# Led7_Segment_Receive.net
KiCad netlist of a schematic drawn in Altium Designer
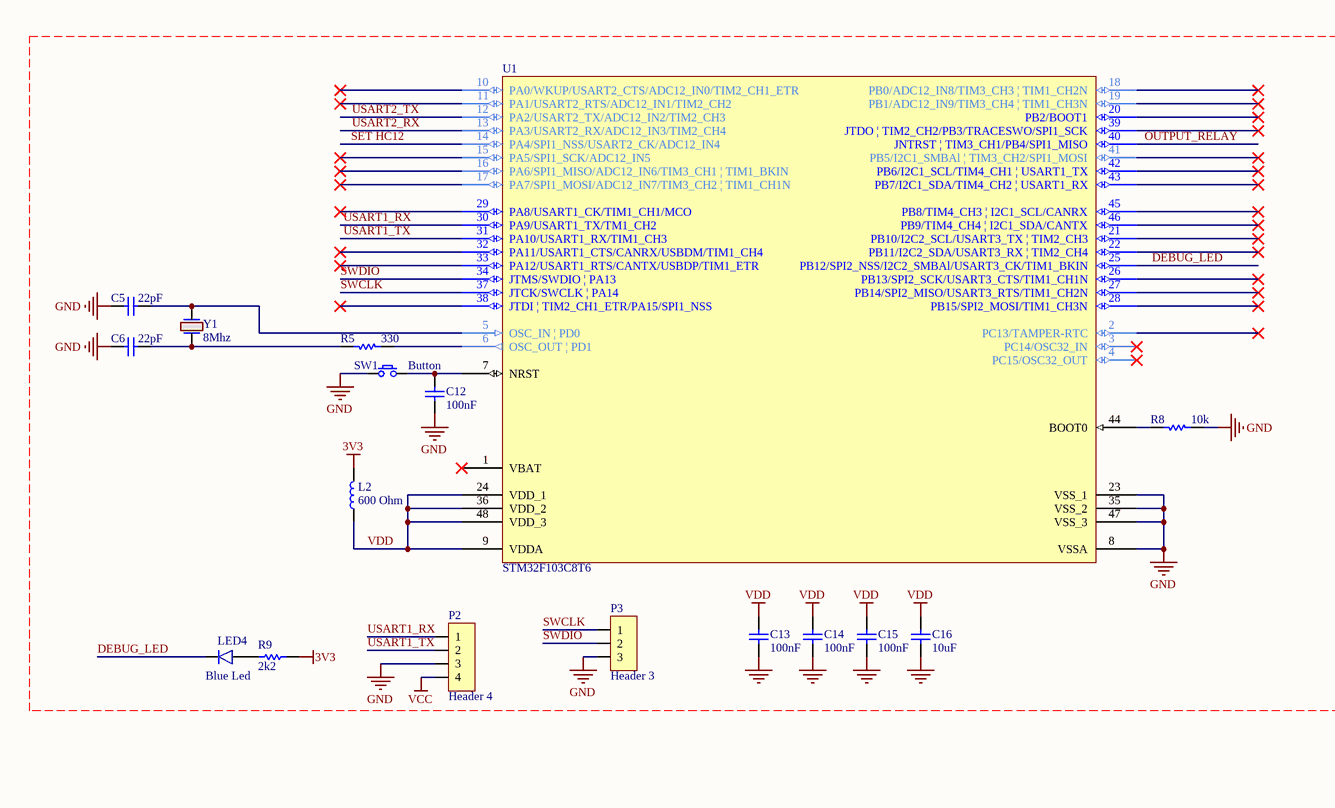
[diagram p0: Led7_Segment_Receive.SchDoc, left]
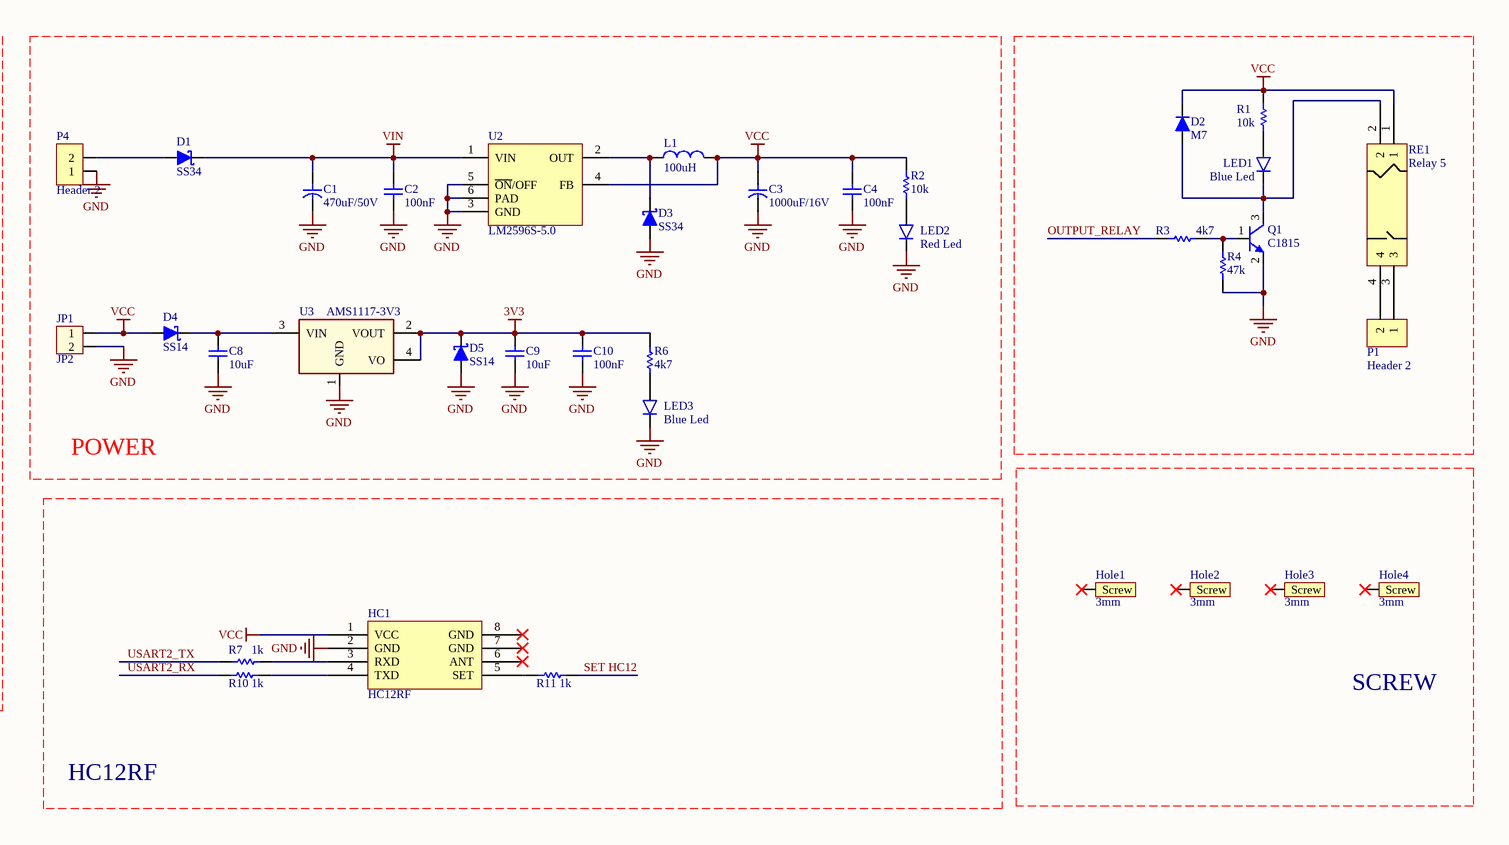
[diagram p1: Led7_Segment_Receive.SchDoc, right]

(export (version "E")
  (design (tool "Eeschema 10.0.6"))
  (components
    (comp (ref "C1")
      (value "470uF/50V")
      (footprint "CR/D.10.0x16.0/P.5.0")
      (description "Capacitor pol")
      (libsource (lib "BKIT4U_LIB") (part "Capacitor"))
    )
    (comp (ref "C2")
      (value "100nF")
      (footprint "C 0805 (2012)")
      (description "Capacitor non-pol")
      (libsource (lib "BKIT4U_LIB") (part "Capacitor NP"))
    )
    (comp (ref "C3")
      (value "1000uF/16V")
      (footprint "CR/D.10.0x12.5/P.5.0")
      (description "Capacitor pol")
      (libsource (lib "BKIT4U_LIB") (part "Capacitor"))
    )
    (comp (ref "C4")
      (value "100nF")
      (footprint "C 0805 (2012)")
      (description "Capacitor non-pol")
      (libsource (lib "BKIT4U_LIB") (part "Capacitor NP"))
    )
    (comp (ref "C5")
      (value "22pF")
      (footprint "C 0805 (2012)")
      (description "Capacitor non-pol")
      (libsource (lib "BKIT4U_LIB") (part "Capacitor NP"))
    )
    (comp (ref "C6")
      (value "22pF")
      (footprint "C 0805 (2012)")
      (description "Capacitor non-pol")
      (libsource (lib "BKIT4U_LIB") (part "Capacitor NP"))
    )
    (comp (ref "C8")
      (value "10uF")
      (footprint "C 0805 (2012)")
      (description "Capacitor non-pol")
      (libsource (lib "BKIT4U_LIB") (part "Capacitor NP"))
    )
    (comp (ref "C9")
      (value "10uF")
      (footprint "C 0805 (2012)")
      (description "Capacitor non-pol")
      (libsource (lib "BKIT4U_LIB") (part "Capacitor NP"))
    )
    (comp (ref "C10")
      (value "100nF")
      (footprint "C 0805 (2012)")
      (description "Capacitor non-pol")
      (libsource (lib "BKIT4U_LIB") (part "Capacitor NP"))
    )
    (comp (ref "C12")
      (value "100nF")
      (footprint "C 0805 (2012)")
      (description "Capacitor non-pol")
      (libsource (lib "BKIT4U_LIB") (part "Capacitor NP"))
    )
    (comp (ref "C13")
      (value "100nF")
      (footprint "C 0805 (2012)")
      (description "Capacitor non-pol")
      (libsource (lib "BKIT4U_LIB") (part "Capacitor NP"))
    )
    (comp (ref "C14")
      (value "100nF")
      (footprint "C 0805 (2012)")
      (description "Capacitor non-pol")
      (libsource (lib "BKIT4U_LIB") (part "Capacitor NP"))
    )
    (comp (ref "C15")
      (value "100nF")
      (footprint "C 0805 (2012)")
      (description "Capacitor non-pol")
      (libsource (lib "BKIT4U_LIB") (part "Capacitor NP"))
    )
    (comp (ref "C16")
      (value "10uF")
      (footprint "C 0805 (2012)")
      (description "Capacitor non-pol")
      (libsource (lib "BKIT4U_LIB") (part "Capacitor NP"))
    )
    (comp (ref "D1")
      (value "SS34")
      (footprint "DO-214AC (SMA)")
      (description "Schottky Diode")
      (fields (field (name "PUBLISHER") "Altium Limited"))
      (libsource (lib "BKIT4U_LIB") (part "Diode Schottky"))
    )
    (comp (ref "D2")
      (value "M7")
      (footprint "DO-214AC (SMA)")
      (description "Default Diode")
      (fields (field (name "PUBLISHER") "Altium Limited"))
      (libsource (lib "BKIT4U_LIB") (part "Diode"))
    )
    (comp (ref "D3")
      (value "SS34")
      (footprint "DO-214AC (SMA)")
      (description "Schottky Diode")
      (fields (field (name "PUBLISHER") "Altium Limited"))
      (libsource (lib "BKIT4U_LIB") (part "Diode Schottky"))
    )
    (comp (ref "D4")
      (value "SS14")
      (footprint "DO-214AC (SMA)")
      (description "Schottky Diode")
      (fields (field (name "PUBLISHER") "Altium Limited"))
      (libsource (lib "BKIT4U_LIB") (part "Diode Schottky"))
    )
    (comp (ref "D5")
      (value "SS14")
      (footprint "DO-214AC (SMA)")
      (description "Schottky Diode")
      (fields (field (name "PUBLISHER") "Altium Limited"))
      (libsource (lib "BKIT4U_LIB") (part "Diode Schottky"))
    )
    (comp (ref "HC1") (value "HC12RF") (footprint "HC12RF") (libsource (lib "BKIT4U_LIB") (part "HC12RF")))
    (comp (ref "Hole1") (value "3mm") (footprint "SCREW/3M/7M") (libsource (lib "BKIT4U_LIB") (part "Screw")))
    (comp (ref "Hole2") (value "3mm") (footprint "SCREW/3M/7M") (libsource (lib "BKIT4U_LIB") (part "Screw")))
    (comp (ref "Hole3") (value "3mm") (footprint "SCREW/3M/7M") (libsource (lib "BKIT4U_LIB") (part "Screw")))
    (comp (ref "Hole4") (value "3mm") (footprint "SCREW/3M/7M") (libsource (lib "BKIT4U_LIB") (part "Screw")))
    (comp (ref "JP1")
      (value "JP2")
      (footprint "CON Header 2")
      (description "Connector 2")
      (libsource (lib "BKIT4U_LIB") (part "Con2"))
    )
    (comp (ref "L1")
      (value "100uH")
      (footprint "Inductor SMD 12x12x8")
      (description "Inductor")
      (libsource (lib "syhaunguyen") (part "L1"))
    )
    (comp (ref "L2")
      (value "600 Ohm")
      (footprint "Inductor SMD 0805 (2012)")
      (description "Inductor")
      (libsource (lib "BKIT4U_LIB") (part "Inductor"))
    )
    (comp (ref "LED1")
      (value "Blue Led")
      (footprint "Led SMD 0805")
      (description "Typical LED")
      (libsource (lib "BKIT4U_LIB") (part "Led"))
    )
    (comp (ref "LED2")
      (value "Red Led")
      (footprint "Led SMD 0805")
      (description "Typical LED")
      (libsource (lib "BKIT4U_LIB") (part "Led"))
    )
    (comp (ref "LED3")
      (value "Blue Led")
      (footprint "Led SMD 0805")
      (description "Typical LED")
      (libsource (lib "BKIT4U_LIB") (part "Led"))
    )
    (comp (ref "LED4")
      (value "Blue Led")
      (footprint "Led SMD 0805")
      (description "Typical LED")
      (libsource (lib "BKIT4U_LIB") (part "Led"))
    )
    (comp (ref "P1")
      (value "Header 2")
      (footprint "HDR Terminal 2")
      (description "Header, 2-Pin")
      (fields (field (name "PUBLISHER") "Altium Limited"))
      (libsource (lib "") (part "Header 2_1"))
    )
    (comp (ref "P2")
      (value "Header 4")
      (footprint "CON Header 4")
      (description "Header, 4-Pin")
      (libsource (lib "BKIT4U_LIB") (part "Header 4"))
    )
    (comp (ref "P3")
      (value "Header 3")
      (footprint "Header 3")
      (description "Header, 3-Pin")
      (libsource (lib "BKIT4U_LIB") (part "Header 3"))
    )
    (comp (ref "P4")
      (value "Header 2")
      (footprint "HDR Domino 2")
      (description "Header, 2-Pin")
      (fields (field (name "PUBLISHER") "Altium Limited"))
      (libsource (lib "BKIT4U_LIB") (part "Header 2"))
    )
    (comp (ref "Q1")
      (value "C1815")
      (footprint "SOT-23")
      (description "NPN Bipolar Transistor")
      (libsource (lib "BKIT4U_LIB") (part "Transistor NPN"))
    )
    (comp (ref "R1")
      (value "10k")
      (footprint "R 0805 (2012)")
      (description "Resistor")
      (fields (field (name "PUBLISHER") "Altium Limited"))
      (libsource (lib "BKIT4U_LIB") (part "Resistor"))
    )
    (comp (ref "R2")
      (value "10k")
      (footprint "R 0805 (2012)")
      (description "Resistor")
      (fields (field (name "PUBLISHER") "Altium Limited"))
      (libsource (lib "BKIT4U_LIB") (part "Resistor"))
    )
    (comp (ref "R3")
      (value "4k7")
      (footprint "R 0805 (2012)")
      (description "Resistor")
      (fields (field (name "PUBLISHER") "Altium Limited"))
      (libsource (lib "BKIT4U_LIB") (part "Resistor"))
    )
    (comp (ref "R4")
      (value "47k")
      (footprint "R 0805 (2012)")
      (description "Resistor")
      (fields (field (name "PUBLISHER") "Altium Limited"))
      (libsource (lib "BKIT4U_LIB") (part "Resistor"))
    )
    (comp (ref "R5")
      (value "330")
      (footprint "R 0805 (2012)")
      (description "Resistor")
      (fields (field (name "PUBLISHER") "Altium Limited"))
      (libsource (lib "BKIT4U_LIB") (part "Resistor"))
    )
    (comp (ref "R6")
      (value "4k7")
      (footprint "R 0805 (2012)")
      (description "Resistor")
      (fields (field (name "PUBLISHER") "Altium Limited"))
      (libsource (lib "BKIT4U_LIB") (part "Resistor"))
    )
    (comp (ref "R7")
      (value "1k")
      (footprint "R 0805 (2012)")
      (description "Resistor")
      (fields (field (name "PUBLISHER") "Altium Limited"))
      (libsource (lib "BKIT4U_LIB") (part "Resistor"))
    )
    (comp (ref "R8")
      (value "10k")
      (footprint "R 0805 (2012)")
      (description "Resistor")
      (fields (field (name "PUBLISHER") "Altium Limited"))
      (libsource (lib "BKIT4U_LIB") (part "Resistor"))
    )
    (comp (ref "R9")
      (value "2k2")
      (footprint "R 0805 (2012)")
      (description "Resistor")
      (fields (field (name "PUBLISHER") "Altium Limited"))
      (libsource (lib "BKIT4U_LIB") (part "Resistor"))
    )
    (comp (ref "R10")
      (value "1k")
      (footprint "R 0805 (2012)")
      (description "Resistor")
      (fields (field (name "PUBLISHER") "Altium Limited"))
      (libsource (lib "BKIT4U_LIB") (part "Resistor"))
    )
    (comp (ref "R11")
      (value "1k")
      (footprint "R 0805 (2012)")
      (description "Resistor")
      (fields (field (name "PUBLISHER") "Altium Limited"))
      (libsource (lib "BKIT4U_LIB") (part "Resistor"))
    )
    (comp (ref "RE1") (value "Relay 5") (footprint "Relay4") (libsource (lib "BKIT4U_LIB") (part "Relay 5")))
    (comp (ref "SW1")
      (value "Button")
      (footprint "SW/2/SMD")
      (description "Tact switch 2 pin")
      (libsource (lib "BKIT4U_LIB") (part "SW SPST"))
    )
    (comp (ref "U1")
      (value "STM32F103C8T6")
      (footprint "LQFP48_N")
      (description "STM32 ARM-based 32-bit MCU with 64 Kbytes Flash, 48-pin LQFP, Industrial Temperature")
      (fields (field (name "PUBLISHER") "Altium Limited"))
      (libsource (lib "BKIT4U_LIB") (part "STM32F103C8T6"))
    )
    (comp (ref "U2")
      (value "LM2596S-5.0")
      (footprint "TO-263-5")
      (description "SIMPLE SWITCHER® 3A Step-Down Voltage Regulator")
      (libsource (lib "BKIT4U_LIB") (part "LM2576/96"))
    )
    (comp (ref "U3")
      (value "AMS1117-3V3")
      (footprint "SOT-223")
      (description "1A LDO Voltage Regulator, ADJ or fixed 1.5/1.8/2.5/2.85/3.3/5V")
      (libsource (lib "BKIT4U_LIB") (part "AMS1117"))
    )
    (comp (ref "Y1")
      (value "8Mhz")
      (footprint "Crystal HC49US SMD")
      (libsource (lib "BKIT4U_LIB") (part "Crystal"))
    )
  )
  (nets
    (net (code "1") (name "/DEBUG_LED") (class "Default")
      (node (ref "LED4") (pin "2") (pinfunction "K_2") (pintype "passive"))
      (node (ref "U1") (pin "25") (pinfunction "PB12/SPI2_NSS/I2C2_SMBAl/USART3_CK/TIM1_BKIN_25") (pintype "bidirectional"))
    )
    (net (code "2") (name "/OUTPUT_RELAY") (class "Default")
      (node (ref "R3") (pin "1") (pinfunction "1_1") (pintype "passive"))
      (node (ref "U1") (pin "40") (pinfunction "JNTRST_¦_TIM3_CH1/PB4/SPI1_MISO_40") (pintype "bidirectional"))
    )
    (net (code "3") (name "/SET HC12") (class "Default")
      (node (ref "R11") (pin "2") (pinfunction "2_2") (pintype "passive"))
      (node (ref "U1") (pin "14") (pinfunction "PA4/SPI1_NSS/USART2_CK/ADC12_IN4_14") (pintype "bidirectional"))
    )
    (net (code "4") (name "/SWCLK") (class "Default")
      (node (ref "P3") (pin "1") (pinfunction "1_1") (pintype "passive"))
      (node (ref "U1") (pin "37") (pinfunction "JTCK/SWCLK_¦_PA14_37") (pintype "bidirectional"))
    )
    (net (code "5") (name "/SWDIO") (class "Default")
      (node (ref "P3") (pin "2") (pinfunction "2_2") (pintype "passive"))
      (node (ref "U1") (pin "34") (pinfunction "JTMS/SWDIO_¦_PA13_34") (pintype "bidirectional"))
    )
    (net (code "6") (name "/USART1_RX") (class "Default")
      (node (ref "P2") (pin "1") (pinfunction "1_1") (pintype "passive"))
      (node (ref "U1") (pin "30") (pinfunction "PA9/USART1_TX/TM1_CH2_30") (pintype "bidirectional"))
    )
    (net (code "7") (name "/USART1_TX") (class "Default")
      (node (ref "P2") (pin "2") (pinfunction "2_2") (pintype "passive"))
      (node (ref "U1") (pin "31") (pinfunction "PA10/USART1_RX/TIM1_CH3_31") (pintype "bidirectional"))
    )
    (net (code "8") (name "/USART2_RX") (class "Default")
      (node (ref "R10") (pin "1") (pinfunction "1_1") (pintype "passive"))
      (node (ref "U1") (pin "13") (pinfunction "PA3/USART2_RX/ADC12_IN3/TIM2_CH4_13") (pintype "bidirectional"))
    )
    (net (code "9") (name "/USART2_TX") (class "Default")
      (node (ref "R7") (pin "1") (pinfunction "1_1") (pintype "passive"))
      (node (ref "U1") (pin "12") (pinfunction "PA2/USART2_TX/ADC12_IN2/TIM2_CH3_12") (pintype "bidirectional"))
    )
    (net (code "10") (name "3V3") (class "Default")
      (node (ref "C10") (pin "1") (pinfunction "1_1") (pintype "passive"))
      (node (ref "C9") (pin "1") (pinfunction "1_1") (pintype "passive"))
      (node (ref "D5") (pin "2") (pinfunction "K_2") (pintype "passive"))
      (node (ref "L2") (pin "2") (pinfunction "2_2") (pintype "passive"))
      (node (ref "R6") (pin "2") (pinfunction "2_2") (pintype "passive"))
      (node (ref "R9") (pin "2") (pinfunction "2_2") (pintype "passive"))
      (node (ref "U3") (pin "2") (pinfunction "VOUT_2") (pintype "passive"))
      (node (ref "U3") (pin "4") (pinfunction "VO_4") (pintype "passive"))
    )
    (net (code "11") (name "GND") (class "Default")
      (node (ref "C1") (pin "2") (pinfunction "2_2") (pintype "passive"))
      (node (ref "C10") (pin "2") (pinfunction "2_2") (pintype "passive"))
      (node (ref "C12") (pin "2") (pinfunction "2_2") (pintype "passive"))
      (node (ref "C13") (pin "2") (pinfunction "2_2") (pintype "passive"))
      (node (ref "C14") (pin "2") (pinfunction "2_2") (pintype "passive"))
      (node (ref "C15") (pin "2") (pinfunction "2_2") (pintype "passive"))
      (node (ref "C16") (pin "2") (pinfunction "2_2") (pintype "passive"))
      (node (ref "C2") (pin "2") (pinfunction "2_2") (pintype "passive"))
      (node (ref "C3") (pin "2") (pinfunction "2_2") (pintype "passive"))
      (node (ref "C4") (pin "2") (pinfunction "2_2") (pintype "passive"))
      (node (ref "C5") (pin "2") (pinfunction "2_2") (pintype "passive"))
      (node (ref "C6") (pin "2") (pinfunction "2_2") (pintype "passive"))
      (node (ref "C8") (pin "2") (pinfunction "2_2") (pintype "passive"))
      (node (ref "C9") (pin "2") (pinfunction "2_2") (pintype "passive"))
      (node (ref "D3") (pin "1") (pinfunction "A_1") (pintype "passive"))
      (node (ref "D5") (pin "1") (pinfunction "A_1") (pintype "passive"))
      (node (ref "HC1") (pin "2") (pinfunction "GND_2") (pintype "passive"))
      (node (ref "JP1") (pin "2") (pinfunction "2_2") (pintype "passive"))
      (node (ref "LED2") (pin "2") (pinfunction "K_2") (pintype "passive"))
      (node (ref "LED3") (pin "2") (pinfunction "K_2") (pintype "passive"))
      (node (ref "P2") (pin "3") (pinfunction "3_3") (pintype "passive"))
      (node (ref "P3") (pin "3") (pinfunction "3_3") (pintype "passive"))
      (node (ref "P4") (pin "1") (pinfunction "1_1") (pintype "passive"))
      (node (ref "Q1") (pin "2") (pinfunction "E_2") (pintype "passive"))
      (node (ref "R4") (pin "1") (pinfunction "1_1") (pintype "passive"))
      (node (ref "R8") (pin "1") (pinfunction "1_1") (pintype "passive"))
      (node (ref "SW1") (pin "1") (pinfunction "1_1") (pintype "passive"))
      (node (ref "U1") (pin "23") (pinfunction "VSS_1_23") (pintype "power_in"))
      (node (ref "U1") (pin "35") (pinfunction "VSS_2_35") (pintype "power_in"))
      (node (ref "U1") (pin "47") (pinfunction "VSS_3_47") (pintype "power_in"))
      (node (ref "U1") (pin "8") (pinfunction "VSSA_8") (pintype "power_in"))
      (node (ref "U2") (pin "3") (pinfunction "GND_3") (pintype "passive"))
      (node (ref "U2") (pin "5") (pinfunction "~{ON}/OFF_5") (pintype "passive"))
      (node (ref "U2") (pin "6") (pinfunction "PAD_6") (pintype "passive"))
      (node (ref "U3") (pin "1") (pinfunction "GND_1") (pintype "passive"))
    )
    (net (code "12") (name "Net-(C6-Pad1)") (class "Default")
      (node (ref "C6") (pin "1") (pinfunction "1_1") (pintype "passive"))
      (node (ref "R5") (pin "2") (pinfunction "2_2") (pintype "passive"))
      (node (ref "Y1") (pin "1") (pinfunction "1_1") (pintype "passive"))
    )
    (net (code "13") (name "Net-(D1-A)") (class "Default")
      (node (ref "D1") (pin "1") (pinfunction "A_1") (pintype "passive"))
      (node (ref "P4") (pin "2") (pinfunction "2_2") (pintype "passive"))
    )
    (net (code "14") (name "Net-(D2-A)") (class "Default")
      (node (ref "D2") (pin "1") (pinfunction "A_1") (pintype "passive"))
      (node (ref "LED1") (pin "2") (pinfunction "K_2") (pintype "passive"))
      (node (ref "Q1") (pin "3") (pinfunction "C_3") (pintype "passive"))
      (node (ref "RE1") (pin "2") (pinfunction "2_2") (pintype "passive"))
    )
    (net (code "15") (name "Net-(D3-K)") (class "Default")
      (node (ref "D3") (pin "2") (pinfunction "K_2") (pintype "passive"))
      (node (ref "L1") (pin "1") (pinfunction "1_1") (pintype "passive"))
      (node (ref "U2") (pin "2") (pinfunction "OUT_2") (pintype "passive"))
    )
    (net (code "16") (name "Net-(D4-K)") (class "Default")
      (node (ref "C8") (pin "1") (pinfunction "1_1") (pintype "passive"))
      (node (ref "D4") (pin "2") (pinfunction "K_2") (pintype "passive"))
      (node (ref "U3") (pin "3") (pinfunction "VIN_3") (pintype "power_in"))
    )
    (net (code "17") (name "Net-(HC1-RXD)") (class "Default")
      (node (ref "HC1") (pin "3") (pinfunction "RXD_3") (pintype "passive"))
      (node (ref "R7") (pin "2") (pinfunction "2_2") (pintype "passive"))
    )
    (net (code "18") (name "Net-(HC1-SET)") (class "Default")
      (node (ref "HC1") (pin "5") (pinfunction "SET_5") (pintype "passive"))
      (node (ref "R11") (pin "1") (pinfunction "1_1") (pintype "passive"))
    )
    (net (code "19") (name "Net-(HC1-TXD)") (class "Default")
      (node (ref "HC1") (pin "4") (pinfunction "TXD_4") (pintype "passive"))
      (node (ref "R10") (pin "2") (pinfunction "2_2") (pintype "passive"))
    )
    (net (code "20") (name "Net-(LED1-A)") (class "Default")
      (node (ref "LED1") (pin "1") (pinfunction "A_1") (pintype "passive"))
      (node (ref "R1") (pin "1") (pinfunction "1_1") (pintype "passive"))
    )
    (net (code "21") (name "Net-(LED2-A)") (class "Default")
      (node (ref "LED2") (pin "1") (pinfunction "A_1") (pintype "passive"))
      (node (ref "R2") (pin "1") (pinfunction "1_1") (pintype "passive"))
    )
    (net (code "22") (name "Net-(LED3-A)") (class "Default")
      (node (ref "LED3") (pin "1") (pinfunction "A_1") (pintype "passive"))
      (node (ref "R6") (pin "1") (pinfunction "1_1") (pintype "passive"))
    )
    (net (code "23") (name "Net-(LED4-A)") (class "Default")
      (node (ref "LED4") (pin "1") (pinfunction "A_1") (pintype "passive"))
      (node (ref "R9") (pin "1") (pinfunction "1_1") (pintype "passive"))
    )
    (net (code "24") (name "Net-(P1-Pad1)") (class "Default")
      (node (ref "P1") (pin "1") (pinfunction "1_1") (pintype "passive"))
      (node (ref "RE1") (pin "3") (pinfunction "3_3") (pintype "passive"))
    )
    (net (code "25") (name "Net-(P1-Pad2)") (class "Default")
      (node (ref "P1") (pin "2") (pinfunction "2_2") (pintype "passive"))
      (node (ref "RE1") (pin "4") (pinfunction "4_4") (pintype "passive"))
    )
    (net (code "26") (name "Net-(Q1-B)") (class "Default")
      (node (ref "Q1") (pin "1") (pinfunction "B_1") (pintype "passive"))
      (node (ref "R3") (pin "2") (pinfunction "2_2") (pintype "passive"))
      (node (ref "R4") (pin "2") (pinfunction "2_2") (pintype "passive"))
    )
    (net (code "27") (name "Net-(U1-BOOT0)") (class "Default")
      (node (ref "R8") (pin "2") (pinfunction "2_2") (pintype "passive"))
      (node (ref "U1") (pin "44") (pinfunction "BOOT0_44") (pintype "input"))
    )
    (net (code "28") (name "Net-(U1-NRST)") (class "Default")
      (node (ref "C12") (pin "1") (pinfunction "1_1") (pintype "passive"))
      (node (ref "SW1") (pin "2") (pinfunction "2_2") (pintype "passive"))
      (node (ref "U1") (pin "7") (pinfunction "NRST_7") (pintype "bidirectional"))
    )
    (net (code "29") (name "Net-(U1-OSC_IN_¦_PD0)") (class "Default")
      (node (ref "C5") (pin "1") (pinfunction "1_1") (pintype "passive"))
      (node (ref "U1") (pin "5") (pinfunction "OSC_IN_¦_PD0_5") (pintype "input"))
      (node (ref "Y1") (pin "2") (pinfunction "2_2") (pintype "passive"))
    )
    (net (code "30") (name "Net-(U1-OSC_OUT_¦_PD1)") (class "Default")
      (node (ref "R5") (pin "1") (pinfunction "1_1") (pintype "passive"))
      (node (ref "U1") (pin "6") (pinfunction "OSC_OUT_¦_PD1_6") (pintype "output"))
    )
    (net (code "31") (name "VCC") (class "Default")
      (node (ref "C3") (pin "1") (pinfunction "1_1") (pintype "passive"))
      (node (ref "C4") (pin "1") (pinfunction "1_1") (pintype "passive"))
      (node (ref "D2") (pin "2") (pinfunction "K_2") (pintype "passive"))
      (node (ref "D4") (pin "1") (pinfunction "A_1") (pintype "passive"))
      (node (ref "HC1") (pin "1") (pinfunction "VCC_1") (pintype "passive"))
      (node (ref "JP1") (pin "1") (pinfunction "1_1") (pintype "passive"))
      (node (ref "L1") (pin "2") (pinfunction "2_2") (pintype "passive"))
      (node (ref "P2") (pin "4") (pinfunction "4_4") (pintype "passive"))
      (node (ref "R1") (pin "2") (pinfunction "2_2") (pintype "passive"))
      (node (ref "R2") (pin "2") (pinfunction "2_2") (pintype "passive"))
      (node (ref "RE1") (pin "1") (pinfunction "1_1") (pintype "passive"))
      (node (ref "U2") (pin "4") (pinfunction "FB_4") (pintype "passive"))
    )
    (net (code "32") (name "VDD") (class "Default")
      (node (ref "C13") (pin "1") (pinfunction "1_1") (pintype "passive"))
      (node (ref "C14") (pin "1") (pinfunction "1_1") (pintype "passive"))
      (node (ref "C15") (pin "1") (pinfunction "1_1") (pintype "passive"))
      (node (ref "C16") (pin "1") (pinfunction "1_1") (pintype "passive"))
      (node (ref "L2") (pin "1") (pinfunction "1_1") (pintype "passive"))
      (node (ref "U1") (pin "24") (pinfunction "VDD_1_24") (pintype "power_in"))
      (node (ref "U1") (pin "36") (pinfunction "VDD_2_36") (pintype "power_in"))
      (node (ref "U1") (pin "48") (pinfunction "VDD_3_48") (pintype "power_in"))
      (node (ref "U1") (pin "9") (pinfunction "VDDA_9") (pintype "power_in"))
    )
    (net (code "33") (name "VIN") (class "Default")
      (node (ref "C1") (pin "1") (pinfunction "1_1") (pintype "passive"))
      (node (ref "C2") (pin "1") (pinfunction "1_1") (pintype "passive"))
      (node (ref "D1") (pin "2") (pinfunction "K_2") (pintype "passive"))
      (node (ref "U2") (pin "1") (pinfunction "VIN_1") (pintype "passive"))
    )
    (net (code "34") (name "unconnected-(HC1-ANT-Pad6)") (class "Default")
      (node (ref "HC1") (pin "6") (pinfunction "ANT_6") (pintype "passive+no_connect"))
    )
    (net (code "35") (name "unconnected-(HC1-GND-Pad7)") (class "Default")
      (node (ref "HC1") (pin "7") (pinfunction "GND_7") (pintype "passive+no_connect"))
    )
    (net (code "36") (name "unconnected-(HC1-GND-Pad8)") (class "Default")
      (node (ref "HC1") (pin "8") (pinfunction "GND_8") (pintype "passive+no_connect"))
    )
    (net (code "37") (name "unconnected-(Hole1-Screw-Pad1)") (class "Default")
      (node (ref "Hole1") (pin "1") (pinfunction "Screw_1") (pintype "passive+no_connect"))
    )
    (net (code "38") (name "unconnected-(Hole2-Screw-Pad1)") (class "Default")
      (node (ref "Hole2") (pin "1") (pinfunction "Screw_1") (pintype "passive+no_connect"))
    )
    (net (code "39") (name "unconnected-(Hole3-Screw-Pad1)") (class "Default")
      (node (ref "Hole3") (pin "1") (pinfunction "Screw_1") (pintype "passive+no_connect"))
    )
    (net (code "40") (name "unconnected-(Hole4-Screw-Pad1)") (class "Default")
      (node (ref "Hole4") (pin "1") (pinfunction "Screw_1") (pintype "passive+no_connect"))
    )
    (net (code "41") (name "unconnected-(U1-JTDI_¦_TIM2_CH1_ETR{slash}PA15{slash}SPI1_NSS-Pad38)") (class "Default")
      (node (ref "U1") (pin "38") (pinfunction "JTDI_¦_TIM2_CH1_ETR/PA15/SPI1_NSS_38") (pintype "bidirectional+no_connect"))
    )
    (net (code "42") (name "unconnected-(U1-JTDO_¦_TIM2_CH2{slash}PB3{slash}TRACESWO{slash}SPI1_SCK-Pad39)") (class "Default")
      (node (ref "U1") (pin "39") (pinfunction "JTDO_¦_TIM2_CH2/PB3/TRACESWO/SPI1_SCK_39") (pintype "bidirectional+no_connect"))
    )
    (net (code "43") (name "unconnected-(U1-PA0{slash}WKUP{slash}USART2_CTS{slash}ADC12_IN0{slash}TIM2_CH1_ETR-Pad10)") (class "Default")
      (node (ref "U1") (pin "10") (pinfunction "PA0/WKUP/USART2_CTS/ADC12_IN0/TIM2_CH1_ETR_10") (pintype "bidirectional+no_connect"))
    )
    (net (code "44") (name "unconnected-(U1-PA1{slash}USART2_RTS{slash}ADC12_IN1{slash}TIM2_CH2-Pad11)") (class "Default")
      (node (ref "U1") (pin "11") (pinfunction "PA1/USART2_RTS/ADC12_IN1/TIM2_CH2_11") (pintype "bidirectional+no_connect"))
    )
    (net (code "45") (name "unconnected-(U1-PA5{slash}SPI1_SCK{slash}ADC12_IN5-Pad15)") (class "Default")
      (node (ref "U1") (pin "15") (pinfunction "PA5/SPI1_SCK/ADC12_IN5_15") (pintype "bidirectional+no_connect"))
    )
    (net (code "46") (name "unconnected-(U1-PA6{slash}SPI1_MISO{slash}ADC12_IN6{slash}TIM3_CH1_¦_TIM1_BKIN-Pad16)") (class "Default")
      (node (ref "U1") (pin "16") (pinfunction "PA6/SPI1_MISO/ADC12_IN6/TIM3_CH1_¦_TIM1_BKIN_16") (pintype "bidirectional+no_connect"))
    )
    (net (code "47") (name "unconnected-(U1-PA7{slash}SPI1_MOSI{slash}ADC12_IN7{slash}TIM3_CH2_¦_TIM1_CH1N-Pad17)") (class "Default")
      (node (ref "U1") (pin "17") (pinfunction "PA7/SPI1_MOSI/ADC12_IN7/TIM3_CH2_¦_TIM1_CH1N_17") (pintype "bidirectional+no_connect"))
    )
    (net (code "48") (name "unconnected-(U1-PA8{slash}USART1_CK{slash}TIM1_CH1{slash}MCO-Pad29)") (class "Default")
      (node (ref "U1") (pin "29") (pinfunction "PA8/USART1_CK/TIM1_CH1/MCO_29") (pintype "bidirectional+no_connect"))
    )
    (net (code "49") (name "unconnected-(U1-PA11{slash}USART1_CTS{slash}CANRX{slash}USBDM{slash}TIM1_CH4-Pad32)") (class "Default")
      (node (ref "U1") (pin "32") (pinfunction "PA11/USART1_CTS/CANRX/USBDM/TIM1_CH4_32") (pintype "bidirectional+no_connect"))
    )
    (net (code "50") (name "unconnected-(U1-PA12{slash}USART1_RTS{slash}CANTX{slash}USBDP{slash}TIM1_ETR-Pad33)") (class "Default")
      (node (ref "U1") (pin "33") (pinfunction "PA12/USART1_RTS/CANTX/USBDP/TIM1_ETR_33") (pintype "bidirectional+no_connect"))
    )
    (net (code "51") (name "unconnected-(U1-PB0{slash}ADC12_IN8{slash}TIM3_CH3_¦_TIM1_CH2N-Pad18)") (class "Default")
      (node (ref "U1") (pin "18") (pinfunction "PB0/ADC12_IN8/TIM3_CH3_¦_TIM1_CH2N_18") (pintype "bidirectional+no_connect"))
    )
    (net (code "52") (name "unconnected-(U1-PB1{slash}ADC12_IN9{slash}TIM3_CH4_¦_TIM1_CH3N-Pad19)") (class "Default")
      (node (ref "U1") (pin "19") (pinfunction "PB1/ADC12_IN9/TIM3_CH4_¦_TIM1_CH3N_19") (pintype "bidirectional+no_connect"))
    )
    (net (code "53") (name "unconnected-(U1-PB2{slash}BOOT1-Pad20)") (class "Default")
      (node (ref "U1") (pin "20") (pinfunction "PB2/BOOT1_20") (pintype "bidirectional+no_connect"))
    )
    (net (code "54") (name "unconnected-(U1-PB5{slash}I2C1_SMBAl_¦_TIM3_CH2{slash}SPI1_MOSI-Pad41)") (class "Default")
      (node (ref "U1") (pin "41") (pinfunction "PB5/I2C1_SMBAl_¦_TIM3_CH2/SPI1_MOSI_41") (pintype "bidirectional+no_connect"))
    )
    (net (code "55") (name "unconnected-(U1-PB6{slash}I2C1_SCL{slash}TIM4_CH1_¦_USART1_TX-Pad42)") (class "Default")
      (node (ref "U1") (pin "42") (pinfunction "PB6/I2C1_SCL/TIM4_CH1_¦_USART1_TX_42") (pintype "bidirectional+no_connect"))
    )
    (net (code "56") (name "unconnected-(U1-PB7{slash}I2C1_SDA{slash}TIM4_CH2_¦_USART1_RX-Pad43)") (class "Default")
      (node (ref "U1") (pin "43") (pinfunction "PB7/I2C1_SDA/TIM4_CH2_¦_USART1_RX_43") (pintype "bidirectional+no_connect"))
    )
    (net (code "57") (name "unconnected-(U1-PB8{slash}TIM4_CH3_¦_I2C1_SCL{slash}CANRX-Pad45)") (class "Default")
      (node (ref "U1") (pin "45") (pinfunction "PB8/TIM4_CH3_¦_I2C1_SCL/CANRX_45") (pintype "bidirectional+no_connect"))
    )
    (net (code "58") (name "unconnected-(U1-PB9{slash}TIM4_CH4_¦_I2C1_SDA{slash}CANTX-Pad46)") (class "Default")
      (node (ref "U1") (pin "46") (pinfunction "PB9/TIM4_CH4_¦_I2C1_SDA/CANTX_46") (pintype "bidirectional+no_connect"))
    )
    (net (code "59") (name "unconnected-(U1-PB10{slash}I2C2_SCL{slash}USART3_TX_¦_TIM2_CH3-Pad21)") (class "Default")
      (node (ref "U1") (pin "21") (pinfunction "PB10/I2C2_SCL/USART3_TX_¦_TIM2_CH3_21") (pintype "bidirectional+no_connect"))
    )
    (net (code "60") (name "unconnected-(U1-PB11{slash}I2C2_SDA{slash}USART3_RX_¦_TIM2_CH4-Pad22)") (class "Default")
      (node (ref "U1") (pin "22") (pinfunction "PB11/I2C2_SDA/USART3_RX_¦_TIM2_CH4_22") (pintype "bidirectional+no_connect"))
    )
    (net (code "61") (name "unconnected-(U1-PB13{slash}SPI2_SCK{slash}USART3_CTS{slash}TIM1_CH1N-Pad26)") (class "Default")
      (node (ref "U1") (pin "26") (pinfunction "PB13/SPI2_SCK/USART3_CTS/TIM1_CH1N_26") (pintype "bidirectional+no_connect"))
    )
    (net (code "62") (name "unconnected-(U1-PB14{slash}SPI2_MISO{slash}USART3_RTS{slash}TIM1_CH2N-Pad27)") (class "Default")
      (node (ref "U1") (pin "27") (pinfunction "PB14/SPI2_MISO/USART3_RTS/TIM1_CH2N_27") (pintype "bidirectional+no_connect"))
    )
    (net (code "63") (name "unconnected-(U1-PB15{slash}SPI2_MOSI{slash}TIM1_CH3N-Pad28)") (class "Default")
      (node (ref "U1") (pin "28") (pinfunction "PB15/SPI2_MOSI/TIM1_CH3N_28") (pintype "bidirectional+no_connect"))
    )
    (net (code "64") (name "unconnected-(U1-PC13{slash}TAMPER-RTC-Pad2)") (class "Default")
      (node (ref "U1") (pin "2") (pinfunction "PC13/TAMPER-RTC_2") (pintype "bidirectional+no_connect"))
    )
    (net (code "65") (name "unconnected-(U1-PC14{slash}OSC32_IN-Pad3)") (class "Default")
      (node (ref "U1") (pin "3") (pinfunction "PC14/OSC32_IN_3") (pintype "bidirectional+no_connect"))
    )
    (net (code "66") (name "unconnected-(U1-PC15{slash}OSC32_OUT-Pad4)") (class "Default")
      (node (ref "U1") (pin "4") (pinfunction "PC15/OSC32_OUT_4") (pintype "bidirectional+no_connect"))
    )
    (net (code "67") (name "unconnected-(U1-VBAT-Pad1)") (class "Default")
      (node (ref "U1") (pin "1") (pinfunction "VBAT_1") (pintype "power_in+no_connect"))
    )
    (net (code "68") (name "unconnected-(U2-GND-Pad6)") (class "Default")
      (node (ref "U2") (pin "6") (pinfunction "GND_6") (pintype "passive"))
    )
  )
)
